# Safety_Status_Indicator.net
KiCad netlist of a schematic drawn in Altium Designer
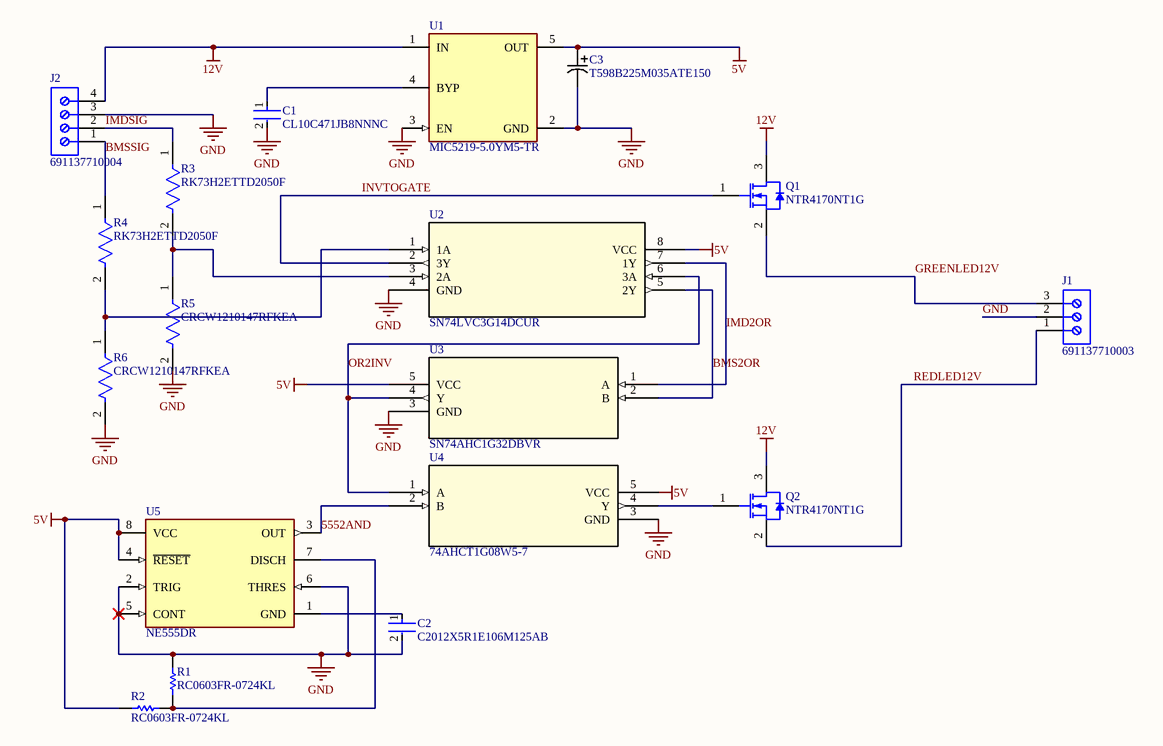
[diagram p0: Safety_Status_Indicator.SchDoc]

(export (version "E")
  (design (tool "Eeschema 10.0.6"))
  (components
    (comp (ref "C1")
      (value "CL10C471JB8NNNC")
      (footprint "FP-CL10-IPC_A")
      (description "Cap Ceramic 470pF 50V C0G ±5% Pad SMD 0603 +125°C T/R")
      (fields (field (name "VOLTAGE") "50V") (field (name "TOLERANCE") "5%"))
      (libsource (lib "Altium Content Vault") (part "b4654b650e69147ec39a6b967a45e02"))
    )
    (comp (ref "C2")
      (value "C2012X5R1E106M125AB")
      (footprint "FP-C2012-125-0_2-MFG")
      (description "Multilayer Ceramic Capacitors 10μF ±20% 25V X5R SMD 0805")
      (fields (field (name "TOLERANCE") "20%"))
      (libsource (lib "Altium Content Vault") (part "b4654b650e69147ec39a6b967a45e02"))
    )
    (comp (ref "C3")
      (value "T598B225M035ATE150")
      (footprint "CAPMP3.7X2.8_2.1N_KEM")
      (description "No Description Available")
      (libsource (lib "T598B225M035ATE150") (part "T598B225M035ATE150"))
    )
    (comp (ref "J1")
      (value "691137710003")
      (footprint "691137710003")
      (description "Series 1377 - 5.00 mm Horizontal Entry with Pressure Clamp WR-TBL, 3 pin")
      (libsource (lib "UWindsor Formula Electric") (part "TBL - 1R - 03P - Screw"))
    )
    (comp (ref "J2")
      (value "691137710004")
      (footprint "691137710004")
      (libsource (lib "Altium Content Vault") (part "TBL - 1R - 04P - Screw"))
    )
    (comp (ref "Q1")
      (value "NTR4170NT1G")
      (footprint "ONSC-SOT-23-3-318-08_V")
      (description "Power MOSFET, 30 V, 3.1 A, Single N-Channe, 3-Pin SOT-23, Pb-Free, Tape and Reel")
      (fields (field (name "MANUFACTURER") "On Semiconductor"))
      (libsource (lib "Altium Content Vault") (part "ONSC-NMOS-G1S2D3-3"))
    )
    (comp (ref "Q2")
      (value "NTR4170NT1G")
      (footprint "ONSC-SOT-23-3-318-08_V")
      (description "Power MOSFET, 30 V, 3.1 A, Single N-Channe, 3-Pin SOT-23, Pb-Free, Tape and Reel")
      (fields (field (name "MANUFACTURER") "On Semiconductor"))
      (libsource (lib "Altium Content Vault") (part "ONSC-NMOS-G1S2D3-3"))
    )
    (comp (ref "R1")
      (value "RC0603FR-0724KL")
      (footprint "RESC1608X55X25NL10T15")
      (fields (field (name "MANUFACTURER") "Yageo"))
      (libsource (lib "Altium Content Vault") (part "RES"))
    )
    (comp (ref "R2")
      (value "RC0603FR-0724KL")
      (footprint "RESC1608X55X25NL10T15")
      (fields (field (name "MANUFACTURER") "Yageo"))
      (libsource (lib "Altium Content Vault") (part "RES"))
    )
    (comp (ref "R3")
      (value "RK73H2ETTD2050F")
      (footprint "FP-RK73H2E-MFG")
      (description "205Ω ±1% 0.5W Chip Resistor 1210 Thick Film AEC-Q200 Qualified")
      (fields (field (name "TOLERANCE") "1%"))
      (libsource (lib "Altium Content Vault") (part "1029c3af85768c4190bb7ad29bc67b5"))
    )
    (comp (ref "R4")
      (value "RK73H2ETTD2050F")
      (footprint "FP-RK73H2E-MFG")
      (description "205Ω ±1% 0.5W Chip Resistor 1210 Thick Film AEC-Q200 Qualified")
      (fields (field (name "TOLERANCE") "1%"))
      (libsource (lib "Altium Content Vault") (part "1029c3af85768c4190bb7ad29bc67b5"))
    )
    (comp (ref "R5")
      (value "CRCW1210147RFKEA")
      (footprint "FP-CRCW1210-e3-IPC_B")
      (description "RES SMD 205K OHM 1% 1/2W 1902")
      (fields (field (name "TOLERANCE") "1%"))
      (libsource (lib "Altium Content Vault") (part "1029c3af85768c4190bb7ad29bc67b5"))
    )
    (comp (ref "R6")
      (value "CRCW1210147RFKEA")
      (footprint "FP-CRCW1210-e3-IPC_B")
      (description "RES SMD 205K OHM 1% 1/2W 1902")
      (fields (field (name "TOLERANCE") "1%"))
      (libsource (lib "Altium Content Vault") (part "1029c3af85768c4190bb7ad29bc67b5"))
    )
    (comp (ref "U1")
      (value "MIC5219-5.0YM5-TR")
      (footprint "FP-SOT23-5LD-PL-1-MFG")
      (description "IC REG LINEAR 5V 500MA SOT23-5")
      (fields
        (field (name "OCTOPART") "https://octopart.com/mic5219-5.0ym5-tr-microchip-66802269")
        (field (name "MANUFACTURER") "Microchip Technology")
      )
      (libsource (lib "Altium Content Vault") (part "ef5decc81e5e4ee52dbbc9c70b739cf"))
    )
    (comp (ref "U2")
      (value "SN74LVC3G14DCUR")
      (footprint "DCU8_TEX")
      (description "No Description Available")
      (libsource (lib "SN74LVC3G14DCUR") (part "SN74LVC3G14DCUR"))
    )
    (comp (ref "U3")
      (value "SN74AHC1G32DBVR")
      (footprint "DBV5")
      (description "Logic OR gate")
      (libsource (lib "SN74AHC1G32DBVR") (part "SN74AHC1G32DBVR"))
    )
    (comp (ref "U4")
      (value "74AHCT1G08W5-7")
      (footprint "SOT25_DIO")
      (description "No Description Available")
      (libsource (lib "74AHCT1G08W5-7") (part "74AHCT1G08W5-7"))
    )
    (comp (ref "U5")
      (value "NE555DR")
      (footprint "FP-D0008A-IPC_A")
      (description "IC OSC SGL TIMER 100KHZ 8-SOIC")
      (libsource (lib "Altium Content Vault") (part "a29bba90211dec1890110b94dad7d53"))
    )
  )
  (nets
    (net (code "1") (name "/5552AND") (class "Default")
      (node (ref "U4") (pin "2") (pinfunction "B_2") (pintype "input"))
      (node (ref "U5") (pin "3") (pinfunction "OUT_3") (pintype "output"))
    )
    (net (code "2") (name "/BMS2OR") (class "Default")
      (node (ref "U2") (pin "5") (pinfunction "2Y_5") (pintype "output"))
      (node (ref "U3") (pin "2") (pinfunction "B_2") (pintype "input"))
    )
    (net (code "3") (name "/BMSSIG") (class "Default")
      (node (ref "J2") (pin "1") (pinfunction "1_1") (pintype "passive"))
      (node (ref "R4") (pin "1") (pinfunction "1_1") (pintype "passive"))
    )
    (net (code "4") (name "/GREENLED12V") (class "Default")
      (node (ref "J1") (pin "3") (pinfunction "3_3") (pintype "passive"))
      (node (ref "Q1") (pin "2") (pinfunction "S_2") (pintype "passive"))
    )
    (net (code "5") (name "/IMD2OR") (class "Default")
      (node (ref "U2") (pin "7") (pinfunction "1Y_7") (pintype "output"))
      (node (ref "U3") (pin "1") (pinfunction "A_1") (pintype "input"))
    )
    (net (code "6") (name "/IMDSIG") (class "Default")
      (node (ref "J2") (pin "2") (pinfunction "2_2") (pintype "passive"))
      (node (ref "R3") (pin "1") (pinfunction "1_1") (pintype "passive"))
    )
    (net (code "7") (name "/INVTOGATE") (class "Default")
      (node (ref "Q1") (pin "1") (pinfunction "G_1") (pintype "passive"))
      (node (ref "U2") (pin "2") (pinfunction "3Y_2") (pintype "output"))
    )
    (net (code "8") (name "/OR2INV") (class "Default")
      (node (ref "U2") (pin "6") (pinfunction "3A_6") (pintype "input"))
      (node (ref "U3") (pin "4") (pinfunction "Y_4") (pintype "output"))
      (node (ref "U4") (pin "1") (pinfunction "A_1") (pintype "input"))
    )
    (net (code "9") (name "/REDLED12V") (class "Default")
      (node (ref "J1") (pin "1") (pinfunction "1_1") (pintype "passive"))
      (node (ref "Q2") (pin "2") (pinfunction "S_2") (pintype "passive"))
    )
    (net (code "10") (name "5V") (class "Default")
      (node (ref "C3") (pin "1") (pinfunction "1_1") (pintype "passive"))
      (node (ref "R2") (pin "1") (pinfunction "1_1") (pintype "passive"))
      (node (ref "U1") (pin "5") (pinfunction "OUT_5") (pintype "power_in"))
      (node (ref "U2") (pin "8") (pinfunction "VCC_8") (pintype "power_in"))
      (node (ref "U3") (pin "5") (pinfunction "VCC_5") (pintype "power_in"))
      (node (ref "U4") (pin "5") (pinfunction "VCC_5") (pintype "power_in"))
      (node (ref "U5") (pin "4") (pinfunction "~{RESET}_4") (pintype "input"))
      (node (ref "U5") (pin "8") (pinfunction "VCC_8") (pintype "power_in"))
    )
    (net (code "11") (name "12V") (class "Default")
      (node (ref "J2") (pin "4") (pinfunction "4_4") (pintype "passive"))
      (node (ref "Q1") (pin "3") (pinfunction "D_3") (pintype "passive"))
      (node (ref "Q2") (pin "3") (pinfunction "D_3") (pintype "passive"))
      (node (ref "U1") (pin "1") (pinfunction "IN_1") (pintype "power_in"))
    )
    (net (code "12") (name "GND") (class "Default")
      (node (ref "C1") (pin "2") (pinfunction "2_2") (pintype "passive"))
      (node (ref "C2") (pin "2") (pinfunction "2_2") (pintype "passive"))
      (node (ref "C3") (pin "2") (pinfunction "2_2") (pintype "passive"))
      (node (ref "J1") (pin "2") (pinfunction "2_2") (pintype "passive"))
      (node (ref "J2") (pin "3") (pinfunction "3_3") (pintype "passive"))
      (node (ref "R1") (pin "2") (pinfunction "2_2") (pintype "passive"))
      (node (ref "R5") (pin "2") (pinfunction "2_2") (pintype "passive"))
      (node (ref "R6") (pin "2") (pinfunction "2_2") (pintype "passive"))
      (node (ref "U1") (pin "2") (pinfunction "GND_2") (pintype "power_in"))
      (node (ref "U1") (pin "3") (pinfunction "EN_3") (pintype "input"))
      (node (ref "U2") (pin "4") (pinfunction "GND_4") (pintype "power_in"))
      (node (ref "U3") (pin "3") (pinfunction "GND_3") (pintype "power_in"))
      (node (ref "U4") (pin "3") (pinfunction "GND_3") (pintype "power_in"))
      (node (ref "U5") (pin "2") (pinfunction "TRIG_2") (pintype "input"))
      (node (ref "U5") (pin "5") (pinfunction "CONT_5") (pintype "input"))
      (node (ref "U5") (pin "6") (pinfunction "THRES_6") (pintype "input"))
    )
    (net (code "13") (name "Net-(Q2-G)") (class "Default")
      (node (ref "Q2") (pin "1") (pinfunction "G_1") (pintype "passive"))
      (node (ref "U4") (pin "4") (pinfunction "Y_4") (pintype "output"))
    )
    (net (code "14") (name "Net-(U1-BYP)") (class "Default")
      (node (ref "C1") (pin "1") (pinfunction "1_1") (pintype "passive"))
      (node (ref "U1") (pin "4") (pinfunction "BYP_4") (pintype "passive"))
    )
    (net (code "15") (name "Net-(U2-1A)") (class "Default")
      (node (ref "R4") (pin "2") (pinfunction "2_2") (pintype "passive"))
      (node (ref "R6") (pin "1") (pinfunction "1_1") (pintype "passive"))
      (node (ref "U2") (pin "1") (pinfunction "1A_1") (pintype "input"))
    )
    (net (code "16") (name "Net-(U2-2A)") (class "Default")
      (node (ref "R3") (pin "2") (pinfunction "2_2") (pintype "passive"))
      (node (ref "R5") (pin "1") (pinfunction "1_1") (pintype "passive"))
      (node (ref "U2") (pin "3") (pinfunction "2A_3") (pintype "input"))
    )
    (net (code "17") (name "Net-(U5-DISCH)") (class "Default")
      (node (ref "R1") (pin "1") (pinfunction "1_1") (pintype "passive"))
      (node (ref "R2") (pin "2") (pinfunction "2_2") (pintype "passive"))
      (node (ref "U5") (pin "7") (pinfunction "DISCH_7") (pintype "open_collector"))
    )
    (net (code "18") (name "Net-(U5-GND)") (class "Default")
      (node (ref "C2") (pin "1") (pinfunction "1_1") (pintype "passive"))
      (node (ref "U5") (pin "1") (pinfunction "GND_1") (pintype "power_in"))
    )
  )
)
